# root.net
KiCad netlist of a schematic drawn in Altium Designer
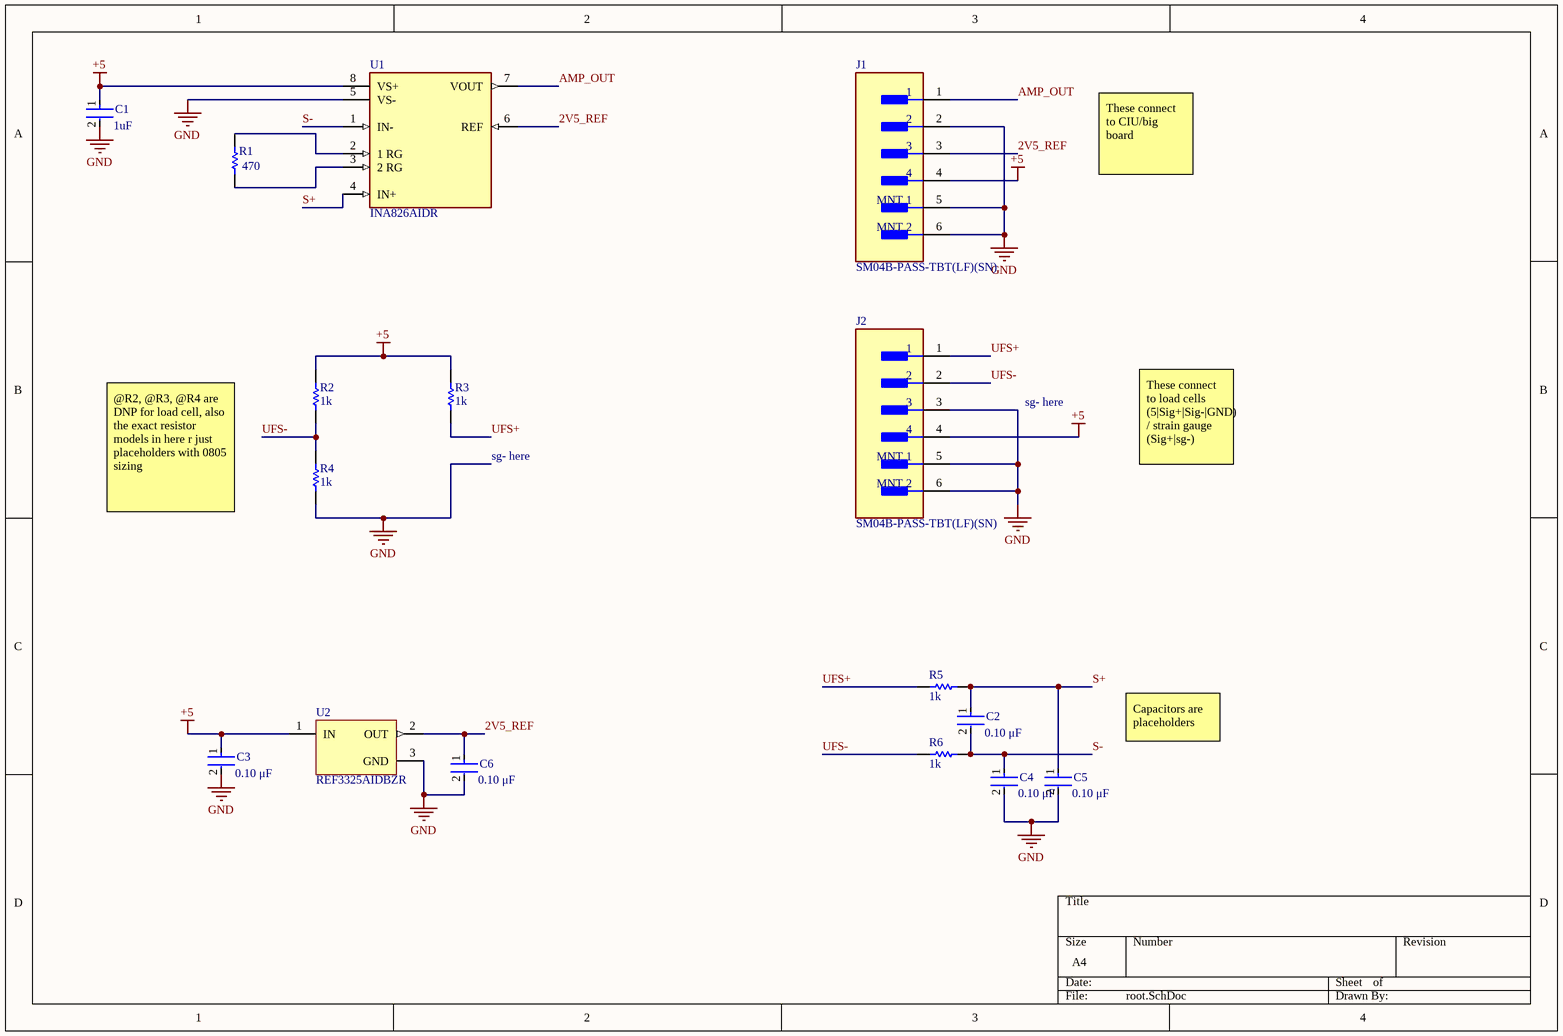
[diagram p0: root.SchDoc]

(export (version "E")
  (design (tool "Eeschema 10.0.6"))
  (components
    (comp (ref "C1")
      (value "CL21B105KBFNNNG")
      (footprint "FP-CL21-IPC_B")
      (description "CL21 Series 0805 1uF 50V ±10% Tolerance X7R Multilayer Ceramic Chip Capacitor")
      (fields
        (field (name "CAPACITANCE") "1uF")
        (field (name "VOLTAGE") "50V")
        (field (name "TOLERANCE") "10%")
      )
      (libsource (lib "Altium Content Vault") (part "b4654b650e69147ec39a6b967a45e02"))
    )
    (comp (ref "C2")
      (value "0.10 μF")
      (footprint "FP-C0805C-DN-IPC_B")
      (description "CAP CER 0.1UF 50V X7R 0805")
      (fields
        (field (name "MANUFACTURER PART NUMBER") "C0805C104K5RACTU")
        (field (name "MANUFACTURER") "KEMET")
      )
      (libsource (lib "Altium Content Vault") (part "b4654b650e69147ec39a6b967a45e02"))
    )
    (comp (ref "C3")
      (value "0.10 μF")
      (footprint "FP-C0805C-DN-IPC_B")
      (description "CAP CER 0.1UF 50V X7R 0805")
      (fields
        (field (name "MANUFACTURER PART NUMBER") "C0805C104K5RACTU")
        (field (name "MANUFACTURER") "KEMET")
      )
      (libsource (lib "Altium Content Vault") (part "b4654b650e69147ec39a6b967a45e02"))
    )
    (comp (ref "C4")
      (value "0.10 μF")
      (footprint "FP-C0805C-DN-IPC_B")
      (description "CAP CER 0.1UF 50V X7R 0805")
      (fields
        (field (name "MANUFACTURER PART NUMBER") "C0805C104K5RACTU")
        (field (name "MANUFACTURER") "KEMET")
      )
      (libsource (lib "Altium Content Vault") (part "b4654b650e69147ec39a6b967a45e02"))
    )
    (comp (ref "C5")
      (value "0.10 μF")
      (footprint "FP-C0805C-DN-IPC_B")
      (description "CAP CER 0.1UF 50V X7R 0805")
      (fields
        (field (name "MANUFACTURER PART NUMBER") "C0805C104K5RACTU")
        (field (name "MANUFACTURER") "KEMET")
      )
      (libsource (lib "Altium Content Vault") (part "b4654b650e69147ec39a6b967a45e02"))
    )
    (comp (ref "C6")
      (value "0.10 μF")
      (footprint "FP-C0805C-DN-IPC_B")
      (description "CAP CER 0.1UF 50V X7R 0805")
      (fields
        (field (name "MANUFACTURER PART NUMBER") "C0805C104K5RACTU")
        (field (name "MANUFACTURER") "KEMET")
      )
      (libsource (lib "Altium Content Vault") (part "b4654b650e69147ec39a6b967a45e02"))
    )
    (comp (ref "J1")
      (value "SM04B-PASS-TBT(LF)(SN)")
      (footprint "FP-SM04B-PASS-TBT_LF_SN-MFG")
      (description "CONN HEADER SMD R/A 4POS 2MM")
      (fields
        (field (name "MANUFACTURER") "JST")
        (field (name "OCTOPART") "https://octopart.com/sm04b-pass-tbt%28lf%29%28sn%29-jst-3990422")
      )
      (libsource (lib "Altium Content Vault") (part "8e3688c4b118bffc0dd9b7401e414ba"))
    )
    (comp (ref "J2")
      (value "SM04B-PASS-TBT(LF)(SN)")
      (footprint "FP-SM04B-PASS-TBT_LF_SN-MFG")
      (description "CONN HEADER SMD R/A 4POS 2MM")
      (fields
        (field (name "MANUFACTURER") "JST")
        (field (name "OCTOPART") "https://octopart.com/sm04b-pass-tbt%28lf%29%28sn%29-jst-3990422")
      )
      (libsource (lib "Altium Content Vault") (part "8e3688c4b118bffc0dd9b7401e414ba"))
    )
    (comp (ref "R1")
      (value "RC0805FR-07470RL")
      (footprint "RESC2013X60X35NL10T20")
      (description "Chip Resistor, 470 Ohm, +/- 1%, 125 mW, -55 to 155 degC, 0805 (2012 Metric), RoHS, Tape and Reel")
      (fields (field (name "MANUFACTURER") "Yageo") (field (name "RESISTANCE") "470"))
      (libsource (lib "Altium Content Vault") (part "RES-2"))
    )
    (comp (ref "R2")
      (value "1k")
      (footprint "RESC2013X60X35NL10T20")
      (fields (field (name "PART NUMBER") "AC0805JR-071KL") (field (name "MANUFACTURER") "Yageo"))
      (libsource (lib "Altium Content Vault") (part "RES"))
    )
    (comp (ref "R3")
      (value "1k")
      (footprint "RESC2013X60X35NL10T20")
      (fields (field (name "PART NUMBER") "AC0805JR-071KL") (field (name "MANUFACTURER") "Yageo"))
      (libsource (lib "Altium Content Vault") (part "RES"))
    )
    (comp (ref "R4")
      (value "1k")
      (footprint "RESC2013X60X35NL10T20")
      (fields (field (name "PART NUMBER") "AC0805JR-071KL") (field (name "MANUFACTURER") "Yageo"))
      (libsource (lib "Altium Content Vault") (part "RES"))
    )
    (comp (ref "R5")
      (value "1k")
      (footprint "RESC2013X60X35NL10T20")
      (fields (field (name "PART NUMBER") "AC0805JR-071KL") (field (name "MANUFACTURER") "Yageo"))
      (libsource (lib "Altium Content Vault") (part "RES"))
    )
    (comp (ref "R6")
      (value "1k")
      (footprint "RESC2013X60X35NL10T20")
      (fields (field (name "PART NUMBER") "AC0805JR-071KL") (field (name "MANUFACTURER") "Yageo"))
      (libsource (lib "Altium Content Vault") (part "RES"))
    )
    (comp (ref "U1")
      (value "INA826AIDR")
      (footprint "FP-D0008A-IPC_A")
      (description "IC INST AMP 1 CIRCUIT 8SOIC")
      (libsource (lib "Altium Content Vault") (part "037b479d141f114d33bcf3e617bad63"))
    )
    (comp (ref "U2")
      (value "REF3325AIDBZR")
      (footprint "DBZ0003A_N")
      (fields (field (name "MANUFACTURER") "Texas Instruments"))
      (libsource (lib "Altium Content Vault") (part "TI-REF3325DBZ3"))
    )
  )
  (nets
    (net (code "1") (name "+5") (class "Default")
      (node (ref "C1") (pin "1") (pinfunction "1_1") (pintype "passive"))
      (node (ref "C3") (pin "1") (pinfunction "1_1") (pintype "passive"))
      (node (ref "J1") (pin "4") (pinfunction "4_4") (pintype "passive"))
      (node (ref "J2") (pin "4") (pinfunction "4_4") (pintype "passive"))
      (node (ref "R2") (pin "2") (pinfunction "2_2") (pintype "passive"))
      (node (ref "R3") (pin "2") (pinfunction "2_2") (pintype "passive"))
      (node (ref "U1") (pin "8") (pinfunction "VS+_8") (pintype "power_in"))
      (node (ref "U2") (pin "1") (pinfunction "IN_1") (pintype "power_in"))
    )
    (net (code "2") (name "/2V5_REF") (class "Default")
      (node (ref "C6") (pin "1") (pinfunction "1_1") (pintype "passive"))
      (node (ref "J1") (pin "3") (pinfunction "3_3") (pintype "passive"))
      (node (ref "U1") (pin "6") (pinfunction "REF_6") (pintype "input"))
      (node (ref "U2") (pin "2") (pinfunction "OUT_2") (pintype "output"))
    )
    (net (code "3") (name "/AMP_OUT") (class "Default")
      (node (ref "J1") (pin "1") (pinfunction "1_1") (pintype "passive"))
      (node (ref "U1") (pin "7") (pinfunction "VOUT_7") (pintype "output"))
    )
    (net (code "4") (name "/S+") (class "Default")
      (node (ref "C2") (pin "1") (pinfunction "1_1") (pintype "passive"))
      (node (ref "C5") (pin "1") (pinfunction "1_1") (pintype "passive"))
      (node (ref "R5") (pin "2") (pinfunction "2_2") (pintype "passive"))
      (node (ref "U1") (pin "4") (pinfunction "IN+_4") (pintype "input"))
    )
    (net (code "5") (name "/S-") (class "Default")
      (node (ref "C2") (pin "2") (pinfunction "2_2") (pintype "passive"))
      (node (ref "C4") (pin "1") (pinfunction "1_1") (pintype "passive"))
      (node (ref "R6") (pin "2") (pinfunction "2_2") (pintype "passive"))
      (node (ref "U1") (pin "1") (pinfunction "IN-_1") (pintype "input"))
    )
    (net (code "6") (name "/UFS+") (class "Default")
      (node (ref "J2") (pin "1") (pinfunction "1_1") (pintype "passive"))
      (node (ref "R3") (pin "1") (pinfunction "1_1") (pintype "passive"))
      (node (ref "R5") (pin "1") (pinfunction "1_1") (pintype "passive"))
    )
    (net (code "7") (name "/UFS-") (class "Default")
      (node (ref "J2") (pin "2") (pinfunction "2_2") (pintype "passive"))
      (node (ref "R2") (pin "1") (pinfunction "1_1") (pintype "passive"))
      (node (ref "R4") (pin "2") (pinfunction "2_2") (pintype "passive"))
      (node (ref "R6") (pin "1") (pinfunction "1_1") (pintype "passive"))
    )
    (net (code "8") (name "GND") (class "Default")
      (node (ref "C1") (pin "2") (pinfunction "2_2") (pintype "passive"))
      (node (ref "C3") (pin "2") (pinfunction "2_2") (pintype "passive"))
      (node (ref "C4") (pin "2") (pinfunction "2_2") (pintype "passive"))
      (node (ref "C5") (pin "2") (pinfunction "2_2") (pintype "passive"))
      (node (ref "C6") (pin "2") (pinfunction "2_2") (pintype "passive"))
      (node (ref "J1") (pin "2") (pinfunction "2_2") (pintype "passive"))
      (node (ref "J1") (pin "5") (pinfunction "MNT_1_5") (pintype "passive"))
      (node (ref "J1") (pin "6") (pinfunction "MNT_2_6") (pintype "passive"))
      (node (ref "J2") (pin "3") (pinfunction "3_3") (pintype "passive"))
      (node (ref "J2") (pin "5") (pinfunction "MNT_1_5") (pintype "passive"))
      (node (ref "J2") (pin "6") (pinfunction "MNT_2_6") (pintype "passive"))
      (node (ref "R4") (pin "1") (pinfunction "1_1") (pintype "passive"))
      (node (ref "U1") (pin "5") (pinfunction "VS-_5") (pintype "power_in"))
      (node (ref "U2") (pin "3") (pinfunction "GND_3") (pintype "power_in"))
    )
    (net (code "9") (name "Net-(U1-1_RG)") (class "Default")
      (node (ref "R1") (pin "2") (pinfunction "2_2") (pintype "passive"))
      (node (ref "U1") (pin "2") (pinfunction "1_RG_2") (pintype "input"))
    )
    (net (code "10") (name "Net-(U1-2_RG)") (class "Default")
      (node (ref "R1") (pin "1") (pinfunction "1_1") (pintype "passive"))
      (node (ref "U1") (pin "3") (pinfunction "2_RG_3") (pintype "input"))
    )
  )
)
